# Polos_y_ceros.net
KiCad netlist of a schematic drawn in Altium Designer
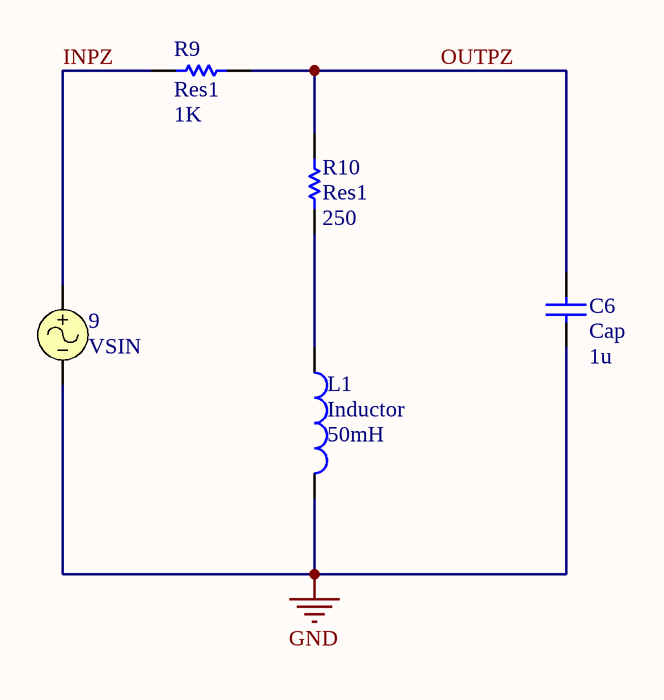
[diagram p0: Polos y ceros.SchDoc]

(export (version "E")
  (design (tool "Eeschema 10.0.6"))
  (components
    (comp (ref "9")
      (value "VSIN")
      (description "Sinusoidal Voltage Source")
      (fields (field (name "PUBLISHER") "Altium Limited"))
      (libsource (lib "Simulation Sources") (part "VSIN"))
    )
    (comp (ref "C6")
      (value "Cap")
      (footprint "RAD-0.3")
      (description "Capacitor")
      (fields (field (name "ALTIUM_VALUE") "1u") (field (name "PUBLISHER") "Altium Limited"))
      (libsource (lib "Miscellaneous Devices") (part "Cap"))
    )
    (comp (ref "L1")
      (value "Inductor")
      (footprint "0402-A")
      (fields (field (name "ALTIUM_VALUE") "50mH") (field (name "PUBLISHER") "Altium Limited"))
      (libsource (lib "Miscellaneous Devices") (part "Inductor"))
    )
    (comp (ref "R9")
      (value "Res1")
      (footprint "AXIAL-0.3")
      (description "Resistor")
      (fields (field (name "ALTIUM_VALUE") "1K") (field (name "PUBLISHER") "Altium Limited"))
      (libsource (lib "Miscellaneous Devices") (part "Res1"))
    )
    (comp (ref "R10")
      (value "Res1")
      (footprint "AXIAL-0.3")
      (description "Resistor")
      (fields (field (name "ALTIUM_VALUE") "250") (field (name "PUBLISHER") "Altium Limited"))
      (libsource (lib "Miscellaneous Devices") (part "Res1"))
    )
  )
  (nets
    (net (code "1") (name "/INPZ") (class "Default")
      (node (ref "9") (pin "1") (pinfunction "1_1") (pintype "passive"))
      (node (ref "R9") (pin "1") (pinfunction "1_1") (pintype "passive"))
    )
    (net (code "2") (name "/OUTPZ") (class "Default")
      (node (ref "C6") (pin "2") (pinfunction "2_2") (pintype "passive"))
      (node (ref "R10") (pin "2") (pinfunction "2_2") (pintype "passive"))
      (node (ref "R9") (pin "2") (pinfunction "2_2") (pintype "passive"))
    )
    (net (code "3") (name "GND") (class "Default")
      (node (ref "9") (pin "2") (pinfunction "2_2") (pintype "passive"))
      (node (ref "C6") (pin "1") (pinfunction "1_1") (pintype "passive"))
      (node (ref "L1") (pin "2") (pinfunction "2_2") (pintype "passive"))
    )
    (net (code "4") (name "Net-(L1-Pad1)") (class "Default")
      (node (ref "L1") (pin "1") (pinfunction "1_1") (pintype "passive"))
      (node (ref "R10") (pin "1") (pinfunction "1_1") (pintype "passive"))
    )
  )
)
